# SFP.net
KiCad netlist of a schematic drawn in Altium Designer
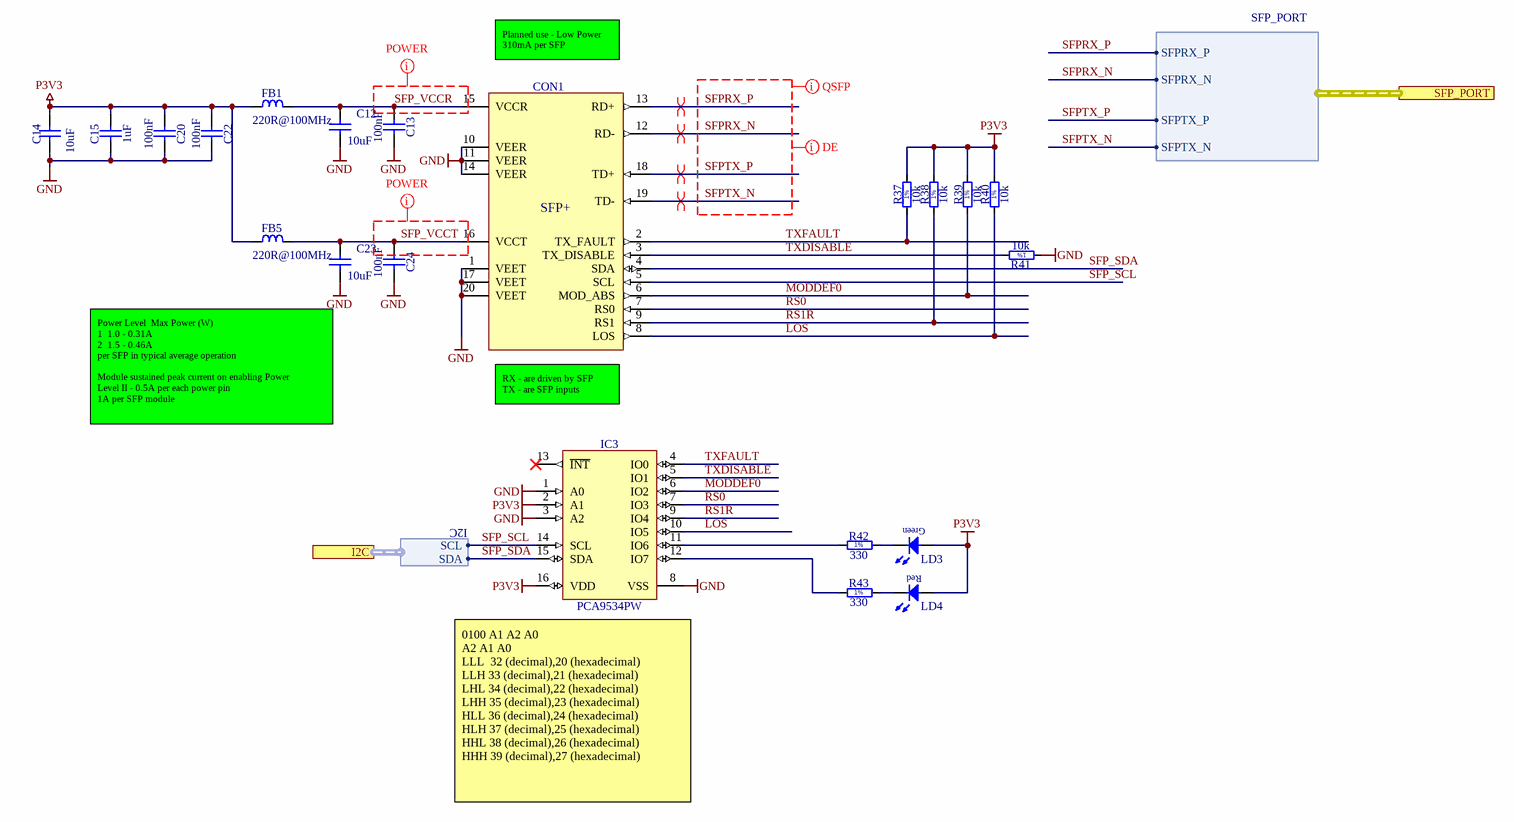
[diagram p0: SFP.SchDoc]

(export (version "E")
  (design (tool "Eeschema 10.0.6"))
  (components
    (comp (ref "C12")
      (value "10uF")
      (footprint "CAPC2012X135N")
      (description "Non-polarised capacitor")
      (fields
        (field (name "PART NUMBER") "CC0805_10UF_10V_10%_X7R")
        (field (name "VOLTAGE") "10V")
        (field (name "AUTHOR") "CERN DEM JLC")
      )
      (libsource (lib "Capacitors") (part "Capacitor - non polarized"))
    )
    (comp (ref "C13")
      (value "100nF")
      (footprint "CAPC1005X55N")
      (description "Non-polarised capacitor")
      (fields
        (field (name "PART NUMBER") "CC0402_100NF_16V_10%_X5R")
        (field (name "VOLTAGE") "16V")
        (field (name "AUTHOR") "CERN DEM JLC")
      )
      (libsource (lib "Capacitors") (part "Capacitor - non polarized"))
    )
    (comp (ref "C14")
      (value "10uF")
      (footprint "CAPC2012X135N")
      (description "Non-polarised capacitor")
      (fields
        (field (name "PART NUMBER") "CC0805_10UF_10V_10%_X7R")
        (field (name "VOLTAGE") "10V")
        (field (name "AUTHOR") "CERN DEM JLC")
      )
      (libsource (lib "Capacitors") (part "Capacitor - non polarized"))
    )
    (comp (ref "C15")
      (value "1uF")
      (footprint "CAPC1608X87N")
      (description "Non-polarised capacitor")
      (fields
        (field (name "PART NUMBER") "CC0603_1UF_25V_10%_X7R")
        (field (name "VOLTAGE") "25V")
        (field (name "AUTHOR") "CERN DEM JLC")
      )
      (libsource (lib "Capacitors") (part "Capacitor - non polarized"))
    )
    (comp (ref "C20")
      (value "100nF")
      (footprint "CAPC1005X55N")
      (description "Non-polarised capacitor")
      (fields
        (field (name "PART NUMBER") "CC0402_100NF_16V_10%_X5R")
        (field (name "VOLTAGE") "16V")
        (field (name "AUTHOR") "CERN DEM JLC")
      )
      (libsource (lib "Capacitors") (part "Capacitor - non polarized"))
    )
    (comp (ref "C22")
      (value "100nF")
      (footprint "CAPC1005X55N")
      (description "Non-polarised capacitor")
      (fields
        (field (name "PART NUMBER") "CC0402_100NF_16V_10%_X5R")
        (field (name "VOLTAGE") "16V")
        (field (name "AUTHOR") "CERN DEM JLC")
      )
      (libsource (lib "Capacitors") (part "Capacitor - non polarized"))
    )
    (comp (ref "C23")
      (value "10uF")
      (footprint "CAPC2012X135N")
      (description "Non-polarised capacitor")
      (fields
        (field (name "PART NUMBER") "CC0805_10UF_10V_10%_X7R")
        (field (name "VOLTAGE") "10V")
        (field (name "AUTHOR") "CERN DEM JLC")
      )
      (libsource (lib "Capacitors") (part "Capacitor - non polarized"))
    )
    (comp (ref "C24")
      (value "100nF")
      (footprint "CAPC1005X55N")
      (description "Non-polarised capacitor")
      (fields
        (field (name "PART NUMBER") "CC0402_100NF_16V_10%_X5R")
        (field (name "VOLTAGE") "16V")
        (field (name "AUTHOR") "CERN DEM JLC")
      )
      (libsource (lib "Capacitors") (part "Capacitor - non polarized"))
    )
    (comp (ref "CON1")
      (value "1888247-1")
      (footprint "TYCO_1888247-1")
      (description "20 Position SFP+ Connector (Small Form-factor Pluggable)")
      (fields
        (field (name "PART NUMBER") "TYCO_1888247-1")
        (field (name "MANUFACTURER") "TYCO ELECTRONICS")
        (field (name "AUTHOR") "CERN DEM JLC")
      )
      (libsource (lib "Connectors") (part "SFP+x1"))
    )
    (comp (ref "FB1")
      (value "220R@100MHz")
      (footprint "INDC2012X105N")
      (description "Inductor")
      (fields
        (field (name "PART NUMBER") "IND0805_MURATA_BLM21PG221SN1D")
        (field (name "POWER") "2A")
        (field (name "AUTHOR") "CERN DEM JLC")
      )
      (libsource (lib "Inductors & Transformers") (part "Inductor"))
    )
    (comp (ref "FB5")
      (value "220R@100MHz")
      (footprint "INDC2012X105N")
      (description "Inductor")
      (fields
        (field (name "PART NUMBER") "IND0805_MURATA_BLM21PG221SN1D")
        (field (name "POWER") "2A")
        (field (name "AUTHOR") "CERN DEM JLC")
      )
      (libsource (lib "Inductors & Transformers") (part "Inductor"))
    )
    (comp (ref "IC3")
      (value "PCA9534PW")
      (footprint "SOP65P640X110-16N")
      (description "8-Bit I2C-Bus and SMBus Low Power I/O Port with Interrupt")
      (fields (field (name "MANUFACTURER") "ANALOG DEVICES") (field (name "AUTHOR") "CERN DEM JLC"))
      (libsource (lib "ICs And Semiconductors") (part "PCA9534PW"))
    )
    (comp (ref "LD3")
      (value "LED_AVAGO_HSME-C120")
      (footprint "LED_AVAGO_HSME-C120")
      (description "LED Green 1C 2A")
      (fields
        (field (name "MANUFACTURER") "AVAGO TECHNOLOGIES")
        (field (name "MANUFACTURER PART NUMBER") "HSME-C120")
        (field (name "AUTHOR") "CERN DEM JMW")
      )
      (libsource (lib "ICs And Semiconductors") (part "LED Green 1C 2A"))
    )
    (comp (ref "LD4")
      (value "Red")
      (footprint "LED_AVAGO_HSME-C120rev")
      (description "LED Red Avago C120")
      (fields
        (field (name "PART NUMBER") "LED_AVAGO_HSMC-C120")
        (field (name "MANUFACTURER") "AVAGO TECHNOLOGIES")
        (field (name "AUTHOR") "CERN DEM JMW")
      )
      (libsource (lib "LIBRARY_SCH") (part "LED_SMD_90deg_mini_R"))
    )
    (comp (ref "R37")
      (value "10k")
      (footprint "RESC1005X40N")
      (description "Resistor - 1%")
      (fields
        (field (name "PART NUMBER") "R0402_10K_1%_0.0625W_100PPM")
        (field (name "POWER") "0.0625W")
        (field (name "AUTHOR") "CERN DEM JLC")
      )
      (libsource (lib "Resistors") (part "Resistor - 1%"))
    )
    (comp (ref "R38")
      (value "10k")
      (footprint "RESC1005X40N")
      (description "Resistor - 1%")
      (fields
        (field (name "PART NUMBER") "R0402_10K_1%_0.0625W_100PPM")
        (field (name "POWER") "0.0625W")
        (field (name "AUTHOR") "CERN DEM JLC")
      )
      (libsource (lib "Resistors") (part "Resistor - 1%"))
    )
    (comp (ref "R39")
      (value "10k")
      (footprint "RESC1005X40N")
      (description "Resistor - 1%")
      (fields
        (field (name "PART NUMBER") "R0402_10K_1%_0.0625W_100PPM")
        (field (name "POWER") "0.0625W")
        (field (name "AUTHOR") "CERN DEM JLC")
      )
      (libsource (lib "Resistors") (part "Resistor - 1%"))
    )
    (comp (ref "R40")
      (value "10k")
      (footprint "RESC1005X40N")
      (description "Resistor - 1%")
      (fields
        (field (name "PART NUMBER") "R0402_10K_1%_0.0625W_100PPM")
        (field (name "POWER") "0.0625W")
        (field (name "AUTHOR") "CERN DEM JLC")
      )
      (libsource (lib "Resistors") (part "Resistor - 1%"))
    )
    (comp (ref "R41")
      (value "10k")
      (footprint "RESC1005X40N")
      (description "Resistor - 1%")
      (fields
        (field (name "PART NUMBER") "R0402_10K_1%_0.0625W_100PPM")
        (field (name "POWER") "0.0625W")
        (field (name "AUTHOR") "CERN DEM JLC")
      )
      (libsource (lib "Resistors") (part "Resistor - 1%"))
    )
    (comp (ref "R42")
      (value "330")
      (footprint "RESC1608X55N")
      (description "Resistor - 1%")
      (fields
        (field (name "PART NUMBER") "R0603_330R_1%_0.1W_100PPM")
        (field (name "POWER") "0.1W")
        (field (name "AUTHOR") "CERN DEM JLC")
      )
      (libsource (lib "Resistors") (part "Resistor - 1%"))
    )
    (comp (ref "R43")
      (value "330")
      (footprint "RESC1608X55N")
      (description "Resistor - 1%")
      (fields
        (field (name "PART NUMBER") "R0603_330R_1%_0.1W_100PPM")
        (field (name "POWER") "0.1W")
        (field (name "AUTHOR") "CERN DEM JLC")
      )
      (libsource (lib "Resistors") (part "Resistor - 1%"))
    )
  )
  (nets
    (net (code "3") (name "/LOS") (class "Default")
      (node (ref "CON1") (pin "8") (pinfunction "LOS_8") (pintype "output"))
      (node (ref "IC3") (pin "10") (pinfunction "IO5_10") (pintype "bidirectional"))
      (node (ref "R40") (pin "1") (pinfunction "1_1") (pintype "passive"))
    )
    (net (code "4") (name "/MODDEF0") (class "Default")
      (node (ref "CON1") (pin "6") (pinfunction "MOD_ABS_6") (pintype "output"))
      (node (ref "IC3") (pin "6") (pinfunction "IO2_6") (pintype "bidirectional"))
      (node (ref "R39") (pin "1") (pinfunction "1_1") (pintype "passive"))
    )
    (net (code "5") (name "/RS0") (class "Default")
      (node (ref "CON1") (pin "7") (pinfunction "RS0_7") (pintype "input"))
      (node (ref "IC3") (pin "7") (pinfunction "IO3_7") (pintype "bidirectional"))
    )
    (net (code "6") (name "/RS1R") (class "Default")
      (node (ref "CON1") (pin "9") (pinfunction "RS1_9") (pintype "input"))
      (node (ref "IC3") (pin "9") (pinfunction "IO4_9") (pintype "bidirectional"))
      (node (ref "R38") (pin "1") (pinfunction "1_1") (pintype "passive"))
    )
    (net (code "7") (name "/SFPRX_N") (class "Default")
      (node (ref "CON1") (pin "12") (pinfunction "RD-_12") (pintype "output"))
    )
    (net (code "8") (name "/SFPRX_P") (class "Default")
      (node (ref "CON1") (pin "13") (pinfunction "RD+_13") (pintype "output"))
    )
    (net (code "9") (name "/SFPTX_N") (class "Default")
      (node (ref "CON1") (pin "19") (pinfunction "TD-_19") (pintype "input"))
    )
    (net (code "10") (name "/SFPTX_P") (class "Default")
      (node (ref "CON1") (pin "18") (pinfunction "TD+_18") (pintype "input"))
    )
    (net (code "11") (name "/SFP_SCL") (class "Default")
      (node (ref "CON1") (pin "5") (pinfunction "SCL_5") (pintype "input"))
      (node (ref "IC3") (pin "14") (pinfunction "SCL_14") (pintype "input"))
    )
    (net (code "12") (name "/SFP_SDA") (class "Default")
      (node (ref "CON1") (pin "4") (pinfunction "SDA_4") (pintype "bidirectional"))
      (node (ref "IC3") (pin "15") (pinfunction "SDA_15") (pintype "bidirectional"))
    )
    (net (code "13") (name "/SFP_VCCR") (class "Default")
      (node (ref "C12") (pin "1") (pinfunction "1_1") (pintype "passive"))
      (node (ref "C13") (pin "1") (pinfunction "1_1") (pintype "passive"))
      (node (ref "CON1") (pin "15") (pinfunction "VCCR_15") (pintype "power_in"))
      (node (ref "FB1") (pin "2") (pinfunction "2_2") (pintype "passive"))
    )
    (net (code "14") (name "/SFP_VCCT") (class "Default")
      (node (ref "C23") (pin "1") (pinfunction "1_1") (pintype "passive"))
      (node (ref "C24") (pin "1") (pinfunction "1_1") (pintype "passive"))
      (node (ref "CON1") (pin "16") (pinfunction "VCCT_16") (pintype "power_in"))
      (node (ref "FB5") (pin "2") (pinfunction "2_2") (pintype "passive"))
    )
    (net (code "15") (name "/TXDISABLE") (class "Default")
      (node (ref "CON1") (pin "3") (pinfunction "TX_DISABLE_3") (pintype "input"))
      (node (ref "IC3") (pin "5") (pinfunction "IO1_5") (pintype "bidirectional"))
      (node (ref "R41") (pin "2") (pinfunction "2_2") (pintype "passive"))
    )
    (net (code "16") (name "/TXFAULT") (class "Default")
      (node (ref "CON1") (pin "2") (pinfunction "TX_FAULT_2") (pintype "output"))
      (node (ref "IC3") (pin "4") (pinfunction "IO0_4") (pintype "bidirectional"))
      (node (ref "R37") (pin "1") (pinfunction "1_1") (pintype "passive"))
    )
    (net (code "19") (name "GND") (class "Default")
      (node (ref "C12") (pin "2") (pinfunction "2_2") (pintype "passive"))
      (node (ref "C13") (pin "2") (pinfunction "2_2") (pintype "passive"))
      (node (ref "C14") (pin "2") (pinfunction "2_2") (pintype "passive"))
      (node (ref "C15") (pin "1") (pinfunction "1_1") (pintype "passive"))
      (node (ref "C20") (pin "2") (pinfunction "2_2") (pintype "passive"))
      (node (ref "C22") (pin "2") (pinfunction "2_2") (pintype "passive"))
      (node (ref "C23") (pin "2") (pinfunction "2_2") (pintype "passive"))
      (node (ref "C24") (pin "2") (pinfunction "2_2") (pintype "passive"))
      (node (ref "CON1") (pin "1") (pinfunction "VEET_1") (pintype "power_in"))
      (node (ref "CON1") (pin "10") (pinfunction "VEER_10") (pintype "power_in"))
      (node (ref "CON1") (pin "11") (pinfunction "VEER_11") (pintype "power_in"))
      (node (ref "CON1") (pin "14") (pinfunction "VEER_14") (pintype "power_in"))
      (node (ref "CON1") (pin "17") (pinfunction "VEET_17") (pintype "power_in"))
      (node (ref "CON1") (pin "20") (pinfunction "VEET_20") (pintype "power_in"))
      (node (ref "IC3") (pin "1") (pinfunction "A0_1") (pintype "input"))
      (node (ref "IC3") (pin "3") (pinfunction "A2_3") (pintype "input"))
      (node (ref "IC3") (pin "8") (pinfunction "VSS_8") (pintype "power_in"))
      (node (ref "R41") (pin "1") (pinfunction "1_1") (pintype "passive"))
    )
    (net (code "20") (name "Net-(IC3-IO6)") (class "Default")
      (node (ref "IC3") (pin "11") (pinfunction "IO6_11") (pintype "bidirectional"))
      (node (ref "R42") (pin "1") (pinfunction "1_1") (pintype "passive"))
    )
    (net (code "21") (name "Net-(IC3-IO7)") (class "Default")
      (node (ref "IC3") (pin "12") (pinfunction "IO7_12") (pintype "bidirectional"))
      (node (ref "R43") (pin "1") (pinfunction "1_1") (pintype "passive"))
    )
    (net (code "22") (name "Net-(LD3-C)") (class "Default")
      (node (ref "LD3") (pin "1") (pinfunction "C_1") (pintype "passive"))
      (node (ref "R42") (pin "2") (pinfunction "2_2") (pintype "passive"))
    )
    (net (code "23") (name "Net-(LD4-C)") (class "Default")
      (node (ref "LD4") (pin "2") (pinfunction "C_2") (pintype "passive"))
      (node (ref "R43") (pin "2") (pinfunction "2_2") (pintype "passive"))
    )
    (net (code "24") (name "P3V3") (class "Default")
      (node (ref "C14") (pin "1") (pinfunction "1_1") (pintype "passive"))
      (node (ref "C15") (pin "2") (pinfunction "2_2") (pintype "passive"))
      (node (ref "C20") (pin "1") (pinfunction "1_1") (pintype "passive"))
      (node (ref "C22") (pin "1") (pinfunction "1_1") (pintype "passive"))
      (node (ref "FB1") (pin "1") (pinfunction "1_1") (pintype "passive"))
      (node (ref "FB5") (pin "1") (pinfunction "1_1") (pintype "passive"))
      (node (ref "IC3") (pin "16") (pinfunction "VDD_16") (pintype "bidirectional"))
      (node (ref "IC3") (pin "2") (pinfunction "A1_2") (pintype "input"))
      (node (ref "LD3") (pin "2") (pinfunction "A_2") (pintype "passive"))
      (node (ref "LD4") (pin "1") (pinfunction "A_1") (pintype "passive"))
      (node (ref "R37") (pin "2") (pinfunction "2_2") (pintype "passive"))
      (node (ref "R38") (pin "2") (pinfunction "2_2") (pintype "passive"))
      (node (ref "R39") (pin "2") (pinfunction "2_2") (pintype "passive"))
      (node (ref "R40") (pin "2") (pinfunction "2_2") (pintype "passive"))
    )
    (net (code "25") (name "unconnected-(IC3-~{INT}-Pad13)") (class "Default")
      (node (ref "IC3") (pin "13") (pinfunction "~{INT}_13") (pintype "output+no_connect"))
    )
  )
)
